# OneDollarComputer_com_1_004_r1.net
KiCad netlist of a schematic drawn in EAGLE
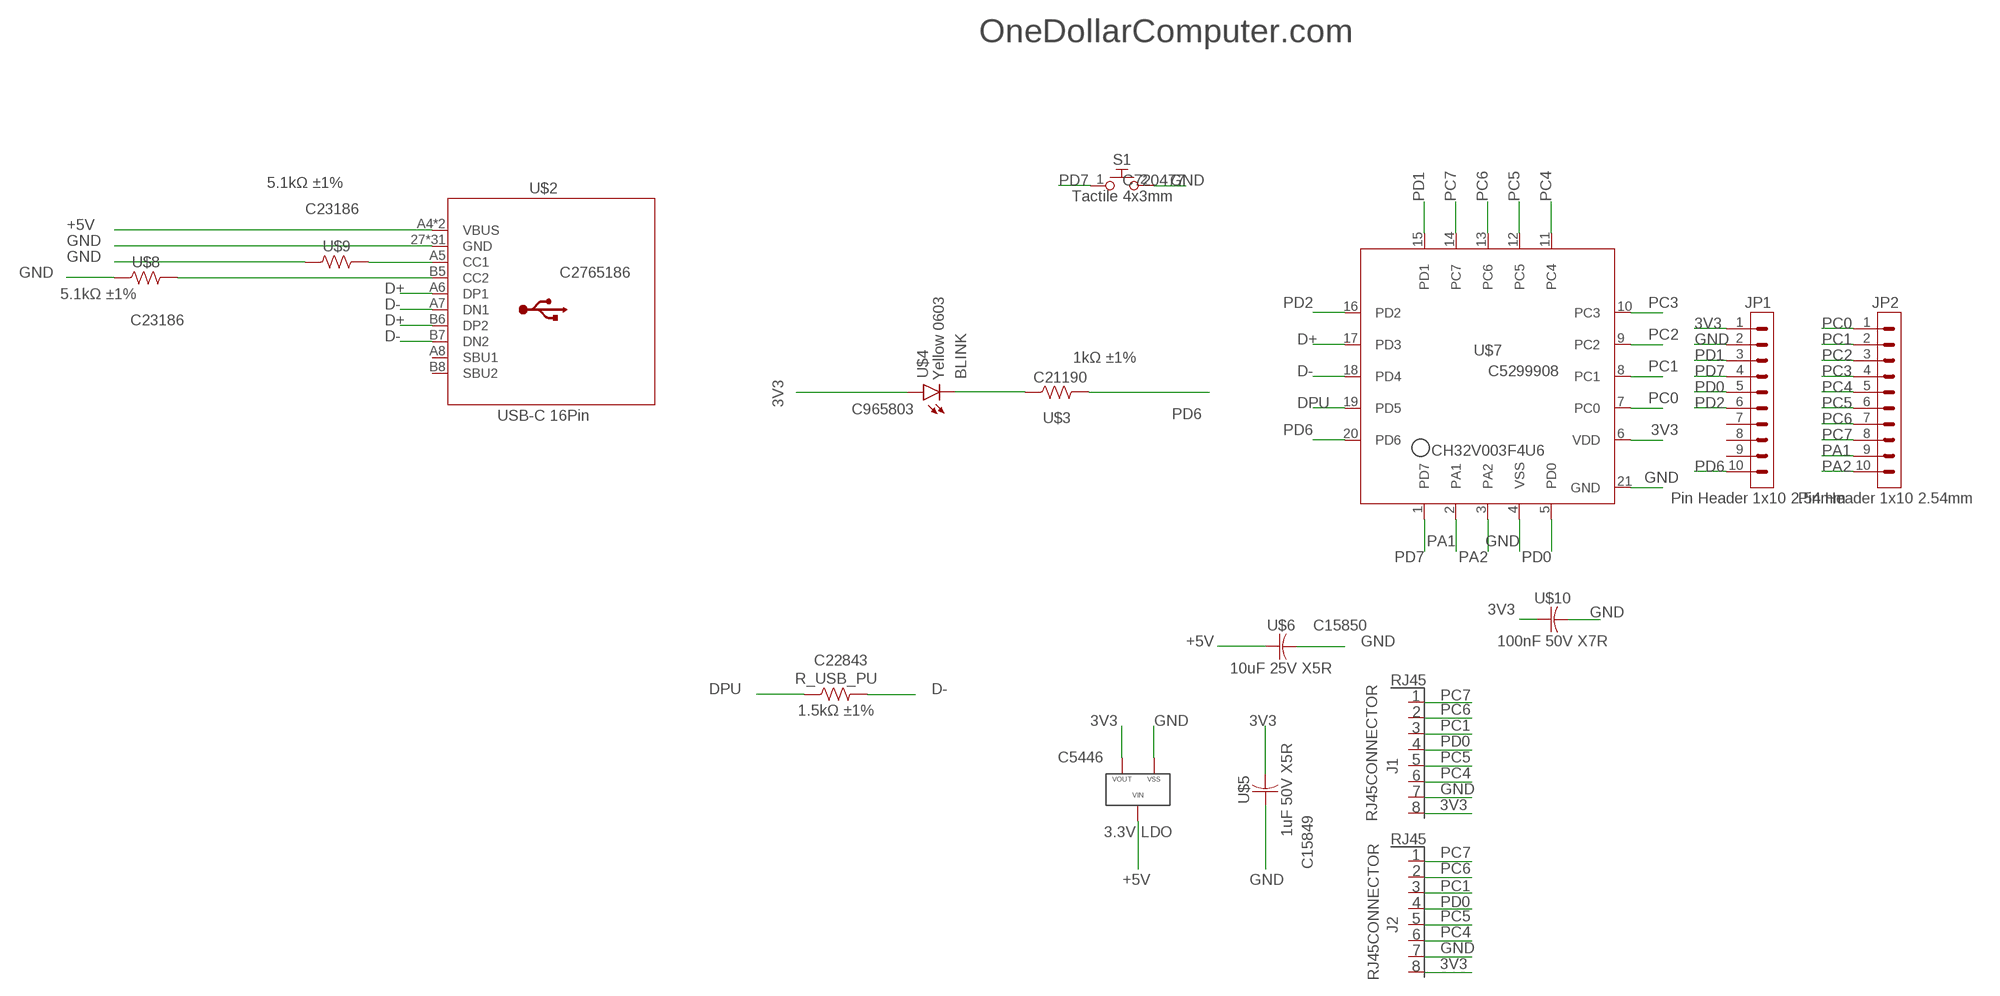
[diagram p0: schematic, sheet 1]

(export (version "E")
  (design (tool "Eeschema 10.0.6"))
  (components
    (comp (ref "J1")
      (value "RJ45CONNECTOR")
      (footprint "eagle-import:2.54_1.0")
      (libsource (lib "eagle-import") (part "RJ45CONNECTOR"))
    )
    (comp (ref "J2")
      (value "RJ45CONNECTOR")
      (footprint "eagle-import:2.54_1.0")
      (libsource (lib "eagle-import") (part "RJ45CONNECTOR"))
    )
    (comp (ref "JP1")
      (value "Pin Header 1x10 2.54mm")
      (footprint "eagle-import:1X10")
      (fields
        (field (name "LCSC_PART") "C350306")
        (field (name "MANUFACTURER") "HOAUC")
        (field (name "MFR_PART") "2685Y-110CNG1SNA01")
      )
      (libsource (lib "eagle-import") (part "PINHD-1X10"))
    )
    (comp (ref "JP2")
      (value "Pin Header 1x10 2.54mm")
      (footprint "eagle-import:1X10")
      (fields
        (field (name "LCSC_PART") "C350306")
        (field (name "MANUFACTURER") "HOAUC")
        (field (name "MFR_PART") "2685Y-110CNG1SNA01")
      )
      (libsource (lib "eagle-import") (part "PINHD-1X10"))
    )
    (comp (ref "R_USB_PU")
      (value "1.5kΩ ±1%")
      (footprint "eagle-import:WRIS-RSKS_0603_WAVE")
      (fields
        (field (name "LCSC_PART") "C22843")
        (field (name "MANUFACTURER") "UNI-ROYAL")
        (field (name "MFR_PART") "0603WAF1501T5E")
        (field (name "LCSC") "C22843")
      )
      (libsource (lib "eagle-import") (part "R_0603_1.5K"))
    )
    (comp (ref "S1")
      (value "Tactile 4x3mm")
      (footprint "eagle-import:B3U-1000P(M)")
      (fields
        (field (name "LCSC_PART") "C720477")
        (field (name "MANUFACTURER") "XUNPU")
        (field (name "MFR_PART") "TS-1088-AR02016")
        (field (name "LCSC") "C720477")
      )
      (libsource (lib "eagle-import") (part "B3U-X0001000P(M)B3U-1000P(M)"))
    )
    (comp (ref "U$1")
      (value "3.3V LDO")
      (footprint "eagle-import:XC6206P332MR-G")
      (fields
        (field (name "LCSC_PART") "C5446")
        (field (name "MANUFACTURER") "TOREX")
        (field (name "MFR_PART") "XC6206P332MR-G")
        (field (name "LCSC") "C5446")
      )
      (libsource (lib "eagle-import") (part "XC6206P332MR-G"))
    )
    (comp (ref "U$2")
      (value "USB-C 16Pin")
      (footprint "eagle-import:CONN_TYPE-C-16P")
      (fields
        (field (name "LCSC_PART") "C2765186")
        (field (name "MANUFACTURER") "SHOU HAN")
        (field (name "MFR_PART") "TYPE-C_16PIN_2MD(073)")
        (field (name "LCSC") "C2765186")
      )
      (libsource (lib "eagle-import") (part "USB-C"))
    )
    (comp (ref "U$3")
      (value "1kΩ ±1%")
      (footprint "eagle-import:RESC2208X45")
      (fields
        (field (name "LCSC_PART") "C21190")
        (field (name "MANUFACTURER") "UNI-ROYAL")
        (field (name "MFR_PART") "0603WAF1001T5E")
        (field (name "LCSC") "C21190")
      )
      (libsource (lib "eagle-import") (part "R_0603_1K_1%_0.1W_C21190"))
    )
    (comp (ref "U$4")
      (value "Yellow 0603")
      (footprint "eagle-import:LEDC1507X40")
      (fields
        (field (name "LCSC_PART") "C965803")
        (field (name "MANUFACTURER") "XINGLIGHT")
        (field (name "MFR_PART") "XL-1608UYC-04")
        (field (name "LCSC") "C965803")
      )
      (libsource (lib "eagle-import") (part "LED"))
    )
    (comp (ref "U$5")
      (value "1uF 50V X5R")
      (footprint "eagle-import:CPA1UF")
      (fields
        (field (name "LCSC_PART") "C15849")
        (field (name "MANUFACTURER") "Samsung Electro-Mechanics")
        (field (name "MFR_PART") "CL10A105KB8NNNC")
        (field (name "LCSC") "C15849")
      )
      (libsource (lib "eagle-import") (part "CAP1UF"))
    )
    (comp (ref "U$6")
      (value "10uF 25V X5R")
      (footprint "eagle-import:CAP0603")
      (fields
        (field (name "LCSC_PART") "C15850")
        (field (name "MANUFACTURER") "Samsung Electro-Mechanics")
        (field (name "MFR_PART") "CL21A106KAYNNNE")
        (field (name "LCSC") "C15850")
      )
      (libsource (lib "eagle-import") (part "CAP10UF"))
    )
    (comp (ref "U$7")
      (value "CH32V003F4U6")
      (footprint "eagle-import:CH32V003F4U6")
      (fields
        (field (name "LCSC_PART") "C5299908")
        (field (name "MANUFACTURER") "WCH")
        (field (name "LCSC") "C5299908")
      )
      (libsource (lib "eagle-import") (part "CH32V003"))
    )
    (comp (ref "U$8")
      (value "5.1kΩ ±1%")
      (footprint "eagle-import:WRIS-RSKS_0603_REFLOW")
      (fields
        (field (name "LCSC_PART") "C23186")
        (field (name "MANUFACTURER") "UNI-ROYAL")
        (field (name "MFR_PART") "0603WAF5101T5E")
        (field (name "LCSC") "C23186")
      )
      (libsource (lib "eagle-import") (part "R_0603_5.1KRES_0603"))
    )
    (comp (ref "U$9")
      (value "5.1kΩ ±1%")
      (footprint "eagle-import:WRIS-RSKS_0603_REFLOW")
      (fields
        (field (name "LCSC_PART") "C23186")
        (field (name "MANUFACTURER") "UNI-ROYAL")
        (field (name "MFR_PART") "0603WAF5101T5E")
        (field (name "LCSC") "C23186")
      )
      (libsource (lib "eagle-import") (part "R_0603_5.1KRES_0603"))
    )
    (comp (ref "U$10")
      (value "100nF 50V X7R")
      (footprint "eagle-import:CAP0603")
      (fields
        (field (name "LCSC_PART") "C30926")
        (field (name "MANUFACTURER") "FH")
        (field (name "MFR_PART") "0603B104K500NT")
      )
      (libsource (lib "eagle-import") (part "CAP100NF"))
    )
  )
  (nets
    (net (code "1") (name "/+5V") (class "Default")
      (node (ref "U$1") (pin "3") (pinfunction "3_3") (pintype "power_in"))
      (node (ref "U$2") (pin "A4") (pinfunction "VBUS_A4") (pintype "power_in"))
      (node (ref "U$2") (pin "B4") (pinfunction "VBUS_B4") (pintype "power_in"))
      (node (ref "U$6") (pin "1") (pinfunction "1_1") (pintype "passive"))
    )
    (net (code "2") (name "/3V3") (class "Default")
      (node (ref "J1") (pin "P$1") (pinfunction "P1_P$1") (pintype "passive"))
      (node (ref "J2") (pin "P$1") (pinfunction "P1_P$1") (pintype "passive"))
      (node (ref "JP1") (pin "1") (pinfunction "1_1") (pintype "passive"))
      (node (ref "U$1") (pin "2") (pinfunction "2_2") (pintype "power_in"))
      (node (ref "U$10") (pin "1") (pinfunction "1_1") (pintype "passive"))
      (node (ref "U$4") (pin "A") (pinfunction "A_A") (pintype "passive"))
      (node (ref "U$5") (pin "2") (pinfunction "2_2") (pintype "passive"))
      (node (ref "U$7") (pin "6") (pinfunction "VDD_6") (pintype "bidirectional"))
    )
    (net (code "3") (name "/BLINK") (class "Default")
      (node (ref "U$3") (pin "1") (pinfunction "1_1") (pintype "passive"))
      (node (ref "U$4") (pin "C") (pinfunction "C_C") (pintype "passive"))
    )
    (net (code "4") (name "/D+") (class "Default")
      (node (ref "U$2") (pin "A6") (pinfunction "DP1_A6") (pintype "bidirectional"))
      (node (ref "U$2") (pin "B6") (pinfunction "DP2_B6") (pintype "bidirectional"))
      (node (ref "U$7") (pin "17") (pinfunction "PD3_17") (pintype "bidirectional"))
    )
    (net (code "5") (name "/D-") (class "Default")
      (node (ref "R_USB_PU") (pin "2") (pinfunction "2_2") (pintype "passive"))
      (node (ref "U$2") (pin "A7") (pinfunction "DN1_A7") (pintype "bidirectional"))
      (node (ref "U$2") (pin "B7") (pinfunction "DN2_B7") (pintype "bidirectional"))
      (node (ref "U$7") (pin "18") (pinfunction "PD4_18") (pintype "bidirectional"))
    )
    (net (code "6") (name "/DPU") (class "Default")
      (node (ref "R_USB_PU") (pin "1") (pinfunction "1_1") (pintype "passive"))
      (node (ref "U$7") (pin "19") (pinfunction "PD5_19") (pintype "power_in"))
    )
    (net (code "7") (name "/GND") (class "Default")
      (node (ref "J1") (pin "P$2") (pinfunction "P2_P$2") (pintype "passive"))
      (node (ref "J2") (pin "P$2") (pinfunction "P2_P$2") (pintype "passive"))
      (node (ref "JP1") (pin "2") (pinfunction "2_2") (pintype "passive"))
      (node (ref "S1") (pin "2") (pinfunction "2_2") (pintype "passive"))
      (node (ref "U$1") (pin "1") (pinfunction "1_1") (pintype "power_in"))
      (node (ref "U$10") (pin "2") (pinfunction "2_2") (pintype "passive"))
      (node (ref "U$2") (pin "27") (pinfunction "GND_27") (pintype "power_in"))
      (node (ref "U$2") (pin "28") (pinfunction "GND_28") (pintype "power_in"))
      (node (ref "U$2") (pin "29") (pinfunction "GND_29") (pintype "power_in"))
      (node (ref "U$2") (pin "30") (pinfunction "GND_30") (pintype "power_in"))
      (node (ref "U$2") (pin "A1") (pinfunction "GND_A1") (pintype "power_in"))
      (node (ref "U$2") (pin "B1") (pinfunction "GND_B1") (pintype "power_in"))
      (node (ref "U$2") (pin "S_1") (pinfunction "GND_S_1") (pintype "power_in"))
      (node (ref "U$2") (pin "S_1_H1") (pinfunction "GND_S_1_H1") (pintype "power_in"))
      (node (ref "U$2") (pin "S_1_H2") (pinfunction "GND_S_1_H2") (pintype "power_in"))
      (node (ref "U$2") (pin "S_2") (pinfunction "GND_S_2") (pintype "power_in"))
      (node (ref "U$2") (pin "S_2_H1") (pinfunction "GND_S_2_H1") (pintype "power_in"))
      (node (ref "U$2") (pin "S_2_H12") (pinfunction "GND_S_2_H12") (pintype "power_in"))
      (node (ref "U$2") (pin "S_2_H13") (pinfunction "GND_S_2_H13") (pintype "power_in"))
      (node (ref "U$2") (pin "S_2_H2") (pinfunction "GND_S_2_H2") (pintype "power_in"))
      (node (ref "U$2") (pin "S_2_H3") (pinfunction "GND_S_2_H3") (pintype "power_in"))
      (node (ref "U$2") (pin "S_2_H4") (pinfunction "GND_S_2_H4") (pintype "power_in"))
      (node (ref "U$2") (pin "S_2_H5") (pinfunction "GND_S_2_H5") (pintype "power_in"))
      (node (ref "U$2") (pin "S_2_H6") (pinfunction "GND_S_2_H6") (pintype "power_in"))
      (node (ref "U$2") (pin "S_2_H7") (pinfunction "GND_S_2_H7") (pintype "power_in"))
      (node (ref "U$2") (pin "S_3") (pinfunction "GND_S_3") (pintype "power_in"))
      (node (ref "U$2") (pin "S_3_H1") (pinfunction "GND_S_3_H1") (pintype "power_in"))
      (node (ref "U$2") (pin "S_3_H2") (pinfunction "GND_S_3_H2") (pintype "power_in"))
      (node (ref "U$2") (pin "S_3_H3") (pinfunction "GND_S_3_H3") (pintype "power_in"))
      (node (ref "U$2") (pin "S_3_H4") (pinfunction "GND_S_3_H4") (pintype "power_in"))
      (node (ref "U$2") (pin "S_3_H5") (pinfunction "GND_S_3_H5") (pintype "power_in"))
      (node (ref "U$2") (pin "S_4") (pinfunction "GND_S_4") (pintype "power_in"))
      (node (ref "U$2") (pin "S_4_H1") (pinfunction "GND_S_4_H1") (pintype "power_in"))
      (node (ref "U$2") (pin "S_4_H2") (pinfunction "GND_S_4_H2") (pintype "power_in"))
      (node (ref "U$2") (pin "S_4_H3") (pinfunction "GND_S_4_H3") (pintype "power_in"))
      (node (ref "U$2") (pin "S_4_H4") (pinfunction "GND_S_4_H4") (pintype "power_in"))
      (node (ref "U$2") (pin "S_4_H5") (pinfunction "GND_S_4_H5") (pintype "power_in"))
      (node (ref "U$5") (pin "1") (pinfunction "1_1") (pintype "passive"))
      (node (ref "U$6") (pin "2") (pinfunction "2_2") (pintype "passive"))
      (node (ref "U$7") (pin "21") (pinfunction "GND_21") (pintype "bidirectional"))
      (node (ref "U$7") (pin "4") (pinfunction "VSS_4") (pintype "bidirectional"))
      (node (ref "U$8") (pin "1") (pinfunction "1_1") (pintype "passive"))
      (node (ref "U$9") (pin "1") (pinfunction "1_1") (pintype "passive"))
    )
    (net (code "8") (name "/PA1") (class "Default")
      (node (ref "JP2") (pin "9") (pinfunction "9_9") (pintype "passive"))
      (node (ref "U$7") (pin "2") (pinfunction "PA1_2") (pintype "bidirectional"))
    )
    (net (code "9") (name "/PA2") (class "Default")
      (node (ref "JP2") (pin "10") (pinfunction "10_10") (pintype "passive"))
      (node (ref "U$7") (pin "3") (pinfunction "PA2_3") (pintype "bidirectional"))
    )
    (net (code "10") (name "/PC0") (class "Default")
      (node (ref "JP2") (pin "1") (pinfunction "1_1") (pintype "passive"))
      (node (ref "U$7") (pin "7") (pinfunction "PC0_7") (pintype "bidirectional"))
    )
    (net (code "11") (name "/PC1") (class "Default")
      (node (ref "J1") (pin "P$6") (pinfunction "P6_P$6") (pintype "passive"))
      (node (ref "J2") (pin "P$6") (pinfunction "P6_P$6") (pintype "passive"))
      (node (ref "JP2") (pin "2") (pinfunction "2_2") (pintype "passive"))
      (node (ref "U$7") (pin "8") (pinfunction "PC1_8") (pintype "bidirectional"))
    )
    (net (code "12") (name "/PC2") (class "Default")
      (node (ref "JP2") (pin "3") (pinfunction "3_3") (pintype "passive"))
      (node (ref "U$7") (pin "9") (pinfunction "PC2_9") (pintype "bidirectional"))
    )
    (net (code "13") (name "/PC3") (class "Default")
      (node (ref "JP2") (pin "4") (pinfunction "4_4") (pintype "passive"))
      (node (ref "U$7") (pin "10") (pinfunction "PC3_10") (pintype "bidirectional"))
    )
    (net (code "14") (name "/PC4") (class "Default")
      (node (ref "J1") (pin "P$3") (pinfunction "P3_P$3") (pintype "passive"))
      (node (ref "J2") (pin "P$3") (pinfunction "P3_P$3") (pintype "passive"))
      (node (ref "JP2") (pin "5") (pinfunction "5_5") (pintype "passive"))
      (node (ref "U$7") (pin "11") (pinfunction "PC4_11") (pintype "bidirectional"))
    )
    (net (code "15") (name "/PC5") (class "Default")
      (node (ref "J1") (pin "P$4") (pinfunction "P4_P$4") (pintype "passive"))
      (node (ref "J2") (pin "P$4") (pinfunction "P4_P$4") (pintype "passive"))
      (node (ref "JP2") (pin "6") (pinfunction "6_6") (pintype "passive"))
      (node (ref "U$7") (pin "12") (pinfunction "PC5_12") (pintype "bidirectional"))
    )
    (net (code "16") (name "/PC6") (class "Default")
      (node (ref "J1") (pin "P$7") (pinfunction "P7_P$7") (pintype "passive"))
      (node (ref "J2") (pin "P$7") (pinfunction "P7_P$7") (pintype "passive"))
      (node (ref "JP2") (pin "7") (pinfunction "7_7") (pintype "passive"))
      (node (ref "U$7") (pin "13") (pinfunction "PC6_13") (pintype "bidirectional"))
    )
    (net (code "17") (name "/PC7") (class "Default")
      (node (ref "J1") (pin "P$8") (pinfunction "P8_P$8") (pintype "passive"))
      (node (ref "J2") (pin "P$8") (pinfunction "P8_P$8") (pintype "passive"))
      (node (ref "JP2") (pin "8") (pinfunction "8_8") (pintype "passive"))
      (node (ref "U$7") (pin "14") (pinfunction "PC7_14") (pintype "bidirectional"))
    )
    (net (code "18") (name "/PD0") (class "Default")
      (node (ref "J1") (pin "P$5") (pinfunction "P5_P$5") (pintype "passive"))
      (node (ref "J2") (pin "P$5") (pinfunction "P5_P$5") (pintype "passive"))
      (node (ref "JP1") (pin "5") (pinfunction "5_5") (pintype "passive"))
      (node (ref "U$7") (pin "5") (pinfunction "PD0_5") (pintype "bidirectional"))
    )
    (net (code "19") (name "/PD1") (class "Default")
      (node (ref "JP1") (pin "3") (pinfunction "3_3") (pintype "passive"))
      (node (ref "U$7") (pin "15") (pinfunction "PD1_15") (pintype "bidirectional"))
    )
    (net (code "20") (name "/PD2") (class "Default")
      (node (ref "JP1") (pin "6") (pinfunction "6_6") (pintype "passive"))
      (node (ref "U$7") (pin "16") (pinfunction "PD2_16") (pintype "bidirectional"))
    )
    (net (code "21") (name "/PD6") (class "Default")
      (node (ref "JP1") (pin "10") (pinfunction "10_10") (pintype "passive"))
      (node (ref "U$3") (pin "2") (pinfunction "2_2") (pintype "passive"))
      (node (ref "U$7") (pin "20") (pinfunction "PD6_20") (pintype "bidirectional"))
    )
    (net (code "22") (name "/PD7") (class "Default")
      (node (ref "JP1") (pin "4") (pinfunction "4_4") (pintype "passive"))
      (node (ref "S1") (pin "1") (pinfunction "1_1") (pintype "passive"))
      (node (ref "U$7") (pin "1") (pinfunction "PD7_1") (pintype "bidirectional"))
    )
    (net (code "23") (name "Net-(U$2-CC1)") (class "Default")
      (node (ref "U$2") (pin "A5") (pinfunction "CC1_A5") (pintype "bidirectional"))
      (node (ref "U$9") (pin "2") (pinfunction "2_2") (pintype "passive"))
    )
    (net (code "24") (name "Net-(U$2-CC2)") (class "Default")
      (node (ref "U$2") (pin "B5") (pinfunction "CC2_B5") (pintype "bidirectional"))
      (node (ref "U$8") (pin "2") (pinfunction "2_2") (pintype "passive"))
    )
    (net (code "25") (name "unconnected-(JP1-Pad7)") (class "Default")
      (node (ref "JP1") (pin "7") (pinfunction "7_7") (pintype "passive"))
    )
    (net (code "26") (name "unconnected-(JP1-Pad8)") (class "Default")
      (node (ref "JP1") (pin "8") (pinfunction "8_8") (pintype "passive"))
    )
    (net (code "27") (name "unconnected-(JP1-Pad9)") (class "Default")
      (node (ref "JP1") (pin "9") (pinfunction "9_9") (pintype "passive"))
    )
    (net (code "28") (name "unconnected-(U$2-SBU1-PadA8)") (class "Default")
      (node (ref "U$2") (pin "A8") (pinfunction "SBU1_A8") (pintype "bidirectional"))
    )
    (net (code "29") (name "unconnected-(U$2-SBU2-PadB8)") (class "Default")
      (node (ref "U$2") (pin "B8") (pinfunction "SBU2_B8") (pintype "bidirectional"))
    )
  )
)
